# teleinfo.net
KiCad netlist of a schematic drawn in EAGLE
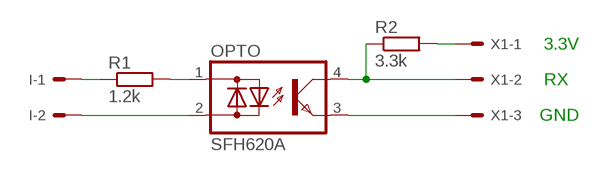
[diagram p0: schematic, sheet 1]

(export (version "E")
  (design (tool "Eeschema 10.0.6"))
  (components
    (comp (ref "I")
      (value "22-23-2021")
      (footprint "eagle-import:22-23-2021")
      (fields (field (name "MF") "MOLEX"))
      (libsource (lib "eagle-import") (part "22-23-2021"))
    )
    (comp (ref "OPTO")
      (value "SFH620A")
      (footprint "eagle-import:DIL04")
      (fields (field (name "MPN") "SFH620A-2"))
      (libsource (lib "eagle-import") (part "SFH620A"))
    )
    (comp (ref "R1")
      (value "1.2k")
      (footprint "eagle-import:0207_12")
      (libsource (lib "eagle-import") (part "R-EU_0207/12"))
    )
    (comp (ref "R2")
      (value "3.3k")
      (footprint "eagle-import:0207_12")
      (libsource (lib "eagle-import") (part "R-EU_0207/12"))
    )
    (comp (ref "X1")
      (value "22-23-2031")
      (footprint "eagle-import:22-23-2031")
      (fields (field (name "MF") "MOLEX"))
      (libsource (lib "eagle-import") (part "22-23-2031"))
    )
  )
  (nets
    (net (code "1") (name "Net-(IA-S)") (class "Default")
      (node (ref "I") (pin "1") (pinfunction "S_1") (pintype "passive"))
      (node (ref "R1") (pin "1") (pinfunction "1_1") (pintype "passive"))
    )
    (net (code "2") (name "Net-(IB-S)") (class "Default")
      (node (ref "I") (pin "2") (pinfunction "S_2") (pintype "passive"))
      (node (ref "OPTO") (pin "2") (pinfunction "AC2_2") (pintype "passive"))
    )
    (net (code "3") (name "Net-(OPTO-AC1)") (class "Default")
      (node (ref "OPTO") (pin "1") (pinfunction "AC1_1") (pintype "passive"))
      (node (ref "R1") (pin "2") (pinfunction "2_2") (pintype "passive"))
    )
    (net (code "4") (name "Net-(OPTO-C)") (class "Default")
      (node (ref "OPTO") (pin "4") (pinfunction "C_4") (pintype "passive"))
      (node (ref "R2") (pin "1") (pinfunction "1_1") (pintype "passive"))
      (node (ref "X1") (pin "2") (pinfunction "S_2") (pintype "passive"))
    )
    (net (code "5") (name "Net-(OPTO-E)") (class "Default")
      (node (ref "OPTO") (pin "3") (pinfunction "E_3") (pintype "passive"))
      (node (ref "X1") (pin "3") (pinfunction "S_3") (pintype "passive"))
    )
    (net (code "6") (name "Net-(X1A-S)") (class "Default")
      (node (ref "R2") (pin "2") (pinfunction "2_2") (pintype "passive"))
      (node (ref "X1") (pin "1") (pinfunction "S_1") (pintype "passive"))
    )
  )
)
